# E17-09-PCU.net
KiCad netlist of a schematic drawn in Altium Designer
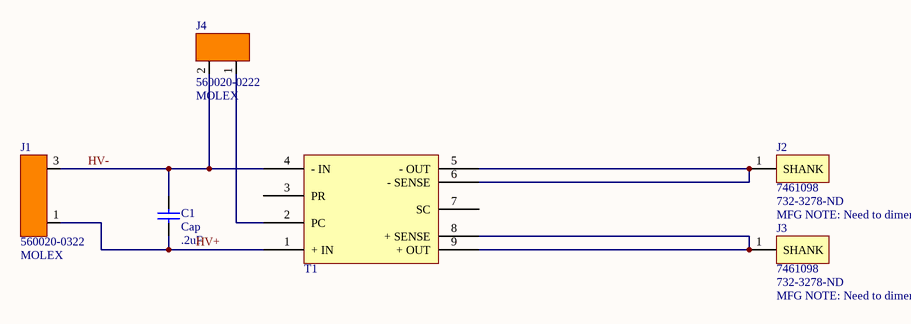
[diagram p0: E17-09-PCU.SchDoc]

(export (version "E")
  (design (tool "Eeschema 10.0.6"))
  (components
    (comp (ref "C1")
      (value "Cap")
      (footprint "B32922H3204")
      (description "Capacitor")
      (fields (field (name "ALTIUM_VALUE") ".2uF") (field (name "PUBLISHER") "Altium Limited"))
      (libsource (lib "Capacitors") (part "Cap"))
    )
    (comp (ref "J1")
      (value "560020-0322_HV")
      (footprint "MOLEX_DURACLIK_3 RED - VERT  HV")
      (description "MOLEX DURACLIK 3-PIN VERT RED HV")
      (fields
        (field (name "VOLTAGE") "250")
        (field (name "MPN") "560020-0322")
        (field (name "MANUFACTURER") "MOLEX")
      )
      (libsource (lib "MolexDuraclik") (part "560020-0322_HV"))
    )
    (comp (ref "J2")
      (value "7461098")
      (footprint "7461098")
      (description "POWER ELEMENT SHANK M6 25PIN")
      (fields
        (field (name "SUPPLIER PART NUMBER 1") "732-3278-ND")
        (field (name "MFG NOTE") "Need to dimension")
      )
      (libsource (lib "Connectors and Headers") (part "7461098"))
    )
    (comp (ref "J3")
      (value "7461098")
      (footprint "7461098")
      (description "POWER ELEMENT SHANK M6 25PIN")
      (fields
        (field (name "SUPPLIER PART NUMBER 1") "732-3278-ND")
        (field (name "MFG NOTE") "Need to dimension")
      )
      (libsource (lib "Connectors and Headers") (part "7461098"))
    )
    (comp (ref "J4")
      (value "560020-0222")
      (footprint "MOLEX_DURACLIK_2 RED VERT")
      (description "MOLEX DURACLIK 2-PIN VERT RED")
      (fields
        (field (name "VOLTAGE") "125")
        (field (name "MPN") "560020-0222")
        (field (name "MANUFACTURER") "MOLEX")
      )
      (libsource (lib "Molex_DuraClik") (part "560020-0222"))
    )
    (comp (ref "T1")
      (value "DC to DC")
      (footprint "PCBComponent_1")
      (description "Isolated DC/DC Converters Maxi Family - Vin - 150, Vout - 12, Power - 500, Product Grade - C")
      (libsource (lib "Modules") (part "DC to DC"))
    )
  )
  (nets
    (net (code "1") (name "/HV+") (class "Default")
      (node (ref "C1") (pin "1") (pinfunction "1_1") (pintype "passive"))
      (node (ref "J1") (pin "1") (pinfunction "1_1") (pintype "passive"))
      (node (ref "T1") (pin "1") (pinfunction "+_IN_1") (pintype "passive"))
    )
    (net (code "2") (name "/HV-") (class "Default")
      (node (ref "C1") (pin "2") (pinfunction "2_2") (pintype "passive"))
      (node (ref "J1") (pin "3") (pinfunction "3_3") (pintype "passive"))
      (node (ref "J4") (pin "2") (pinfunction "2_2") (pintype "passive"))
      (node (ref "T1") (pin "4") (pinfunction "-_IN_4") (pintype "passive"))
    )
    (net (code "3") (name "Net-(J2-SHANK)") (class "Default")
      (node (ref "J2") (pin "1") (pinfunction "SHANK_1") (pintype "passive"))
      (node (ref "T1") (pin "5") (pinfunction "-_OUT_5") (pintype "passive"))
      (node (ref "T1") (pin "6") (pinfunction "-_SENSE_6") (pintype "passive"))
    )
    (net (code "4") (name "Net-(J3-SHANK)") (class "Default")
      (node (ref "J3") (pin "1") (pinfunction "SHANK_1") (pintype "passive"))
      (node (ref "T1") (pin "8") (pinfunction "+_SENSE_8") (pintype "passive"))
      (node (ref "T1") (pin "9") (pinfunction "+_OUT_9") (pintype "passive"))
    )
    (net (code "5") (name "Net-(T1-PC)") (class "Default")
      (node (ref "J4") (pin "1") (pinfunction "1_1") (pintype "passive"))
      (node (ref "T1") (pin "2") (pinfunction "PC_2") (pintype "passive"))
    )
    (net (code "6") (name "unconnected-(T1-PR-Pad3)") (class "Default")
      (node (ref "T1") (pin "3") (pinfunction "PR_3") (pintype "passive"))
    )
    (net (code "7") (name "unconnected-(T1-SC-Pad7)") (class "Default")
      (node (ref "T1") (pin "7") (pinfunction "SC_7") (pintype "passive"))
    )
  )
)
